# Mega8515_flasher_v2.net
KiCad netlist of a schematic drawn in Altium Designer
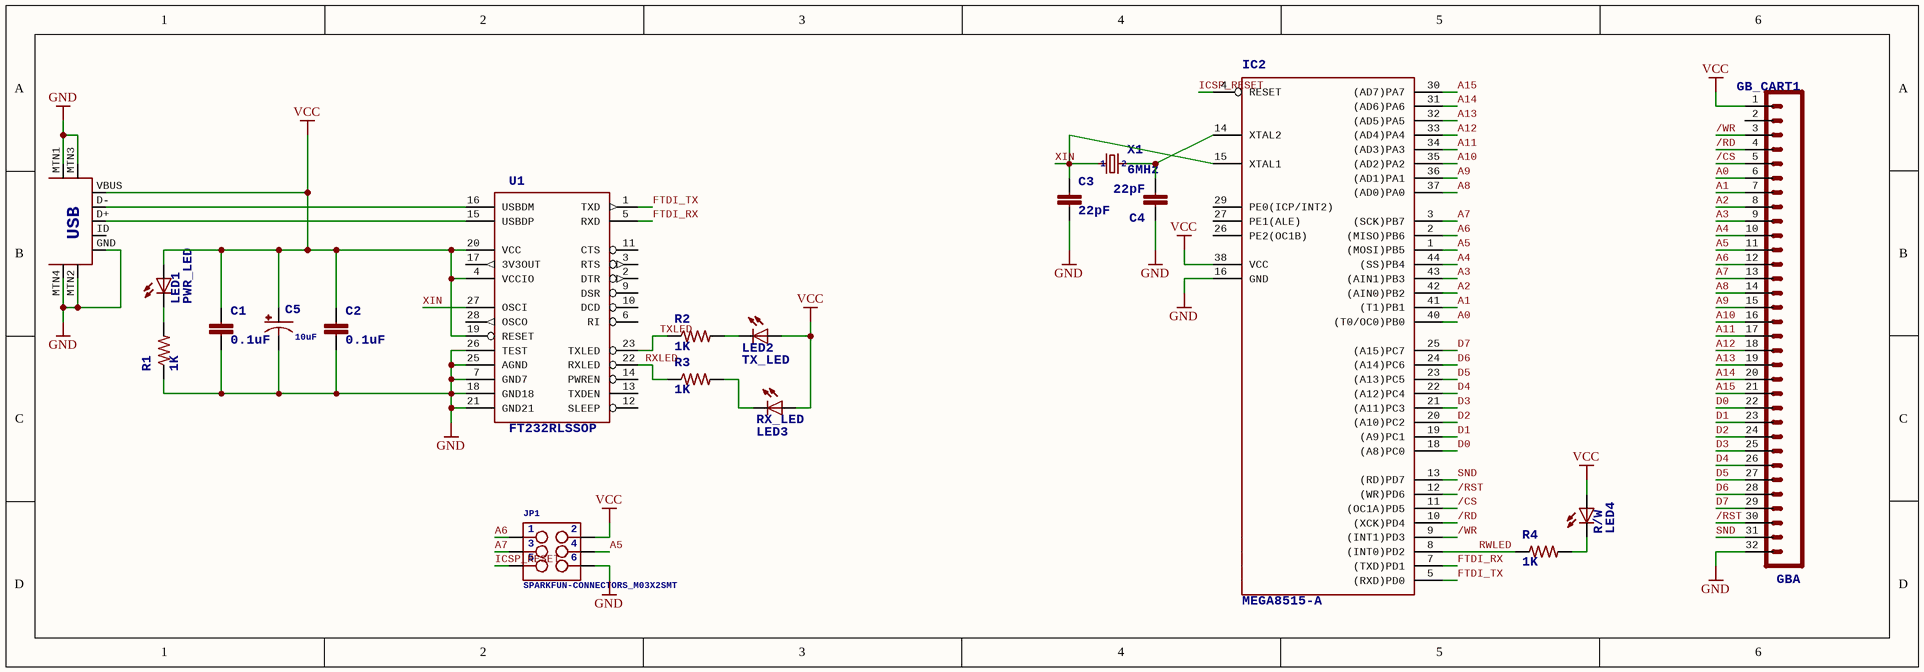
[diagram p0: Mega8515_flasher_v2.SchDoc]

(export (version "E")
  (design (tool "Eeschema 10.0.6"))
  (components
    (comp (ref "C1")
      (value "0.1uF")
      (footprint "0805")
      (description "<b>Capacitor</b>\nStandard 0603 ceramic capacitor, and 0.1\" leaded capacitor.")
      (fields (field (name ">NAME") "C1") (field (name ">VALUE") "0.1uF"))
      (libsource (lib "SparkFun-Capacitors") (part "CAP1206"))
    )
    (comp (ref "C2")
      (value "0.1uF")
      (footprint "0805")
      (description "<b>Capacitor</b>\nStandard 0603 ceramic capacitor, and 0.1\" leaded capacitor.")
      (fields (field (name ">NAME") "C2") (field (name ">VALUE") "0.1uF"))
      (libsource (lib "SparkFun-Capacitors") (part "CAP1206"))
    )
    (comp (ref "C3")
      (value "22pF")
      (footprint "0805")
      (description "<b>Capacitor</b>\nStandard 0603 ceramic capacitor, and 0.1\" leaded capacitor.")
      (fields (field (name ">NAME") "C3") (field (name ">VALUE") "22pF"))
      (libsource (lib "") (part "CAP0805_1"))
    )
    (comp (ref "C4")
      (value "22pF")
      (footprint "0805")
      (description "<b>Capacitor</b>\nStandard 0603 ceramic capacitor, and 0.1\" leaded capacitor.")
      (fields (field (name ">NAME") "C4") (field (name ">VALUE") "22pF"))
      (libsource (lib "SparkFun-Capacitors") (part "CAP0805"))
    )
    (comp (ref "C5")
      (value "10uF")
      (footprint "EIA3216")
      (description "10uF Tantalum SMT<br>\nCAP-00811- 16V 10% (EIA-3216)")
      (fields (field (name ">NAME") "C5"))
      (libsource (lib "SparkFun-Capacitors") (part "10UF-TANT"))
    )
    (comp (ref "GBA")
      (value "GB_CART1")
      (footprint "GB_CART_1")
      (fields (field (name ">VALUE") "GB_CART1") (field (name ">NAME") "GBA"))
      (libsource (lib "alex") (part "GB_CART1"))
    )
    (comp (ref "IC2")
      (value "MEGA8515-A")
      (footprint "TQFP44")
      (fields
        (field (name "MPN") "ATMEGA8515-16AU")
        (field (name ">NAME") "IC2")
        (field (name ">VALUE") "MEGA8515-A")
      )
      (libsource (lib "atmel") (part "MEGA8515-A"))
    )
    (comp (ref "JP1")
      (value "SPARKFUN-CONNECTORS_M03X2SMT")
      (footprint "HDR2X3")
      (fields
        (field (name ">NAME") "JP1")
        (field (name ">VALUE") "SPARKFUN-CONNECTORS_M03X2SMT")
        (field (name "1") "1")
        (field (name "2") "2")
        (field (name "3") "3")
        (field (name "4") "4")
        (field (name "5") "5")
        (field (name "6") "6")
      )
      (libsource (lib "Mega8515_flasher") (part "SPARKFUN-CONNECTORS_M03X2SMT"))
    )
    (comp (ref "LED1")
      (value "PWR_LED")
      (footprint "LED-1206")
      (fields (field (name ">NAME") "LED1") (field (name ">VALUE") "PWR_LED"))
      (libsource (lib "SparkFun-LED") (part "LED1206"))
    )
    (comp (ref "LED2")
      (value "TX_LED")
      (footprint "LED-1206")
      (fields (field (name ">NAME") "LED2") (field (name ">VALUE") "TX_LED"))
      (libsource (lib "SparkFun-LED") (part "LED1206"))
    )
    (comp (ref "R/W")
      (value "LED4")
      (footprint "LED-1206")
      (fields (field (name ">NAME") "R/W") (field (name ">VALUE") "LED4"))
      (libsource (lib "SparkFun-LED") (part "LED1206"))
    )
    (comp (ref "R1")
      (value "1K")
      (footprint "0805")
      (description "<b>Resistor</b>\nBasic schematic elements and footprints for 0603, 1206, and PTH resistors.")
      (fields (field (name ">NAME") "R1") (field (name ">VALUE") "1K"))
      (libsource (lib "SparkFun-Resistors") (part "RESISTOR1206"))
    )
    (comp (ref "R2")
      (value "1K")
      (footprint "0805")
      (description "<b>Resistor</b>\nBasic schematic elements and footprints for 0603, 1206, and PTH resistors.")
      (fields (field (name ">NAME") "R2") (field (name ">VALUE") "1K"))
      (libsource (lib "SparkFun-Resistors") (part "RESISTOR1206"))
    )
    (comp (ref "R3")
      (value "1K")
      (footprint "0805")
      (description "<b>Resistor</b>\nBasic schematic elements and footprints for 0603, 1206, and PTH resistors.")
      (fields (field (name ">NAME") "R3") (field (name ">VALUE") "1K"))
      (libsource (lib "SparkFun-Resistors") (part "RESISTOR1206"))
    )
    (comp (ref "R4")
      (value "1K")
      (footprint "0805")
      (description "<b>Resistor</b>\nBasic schematic elements and footprints for 0603, 1206, and PTH resistors.")
      (fields (field (name ">NAME") "R4") (field (name ">VALUE") "1K"))
      (libsource (lib "SparkFun-Resistors") (part "RESISTOR1206"))
    )
    (comp (ref "RX_LED")
      (value "LED3")
      (footprint "LED-1206")
      (fields (field (name ">NAME") "RX_LED") (field (name ">VALUE") "LED3"))
      (libsource (lib "SparkFun-LED") (part "LED1206"))
    )
    (comp (ref "U1")
      (value "FT232RLSSOP")
      (footprint "SSOP28DB")
      (fields (field (name ">NAME") "U1") (field (name ">VALUE") "FT232RLSSOP"))
      (libsource (lib "SparkFun-DigitalIC") (part "FT232RLSSOP"))
    )
    (comp (ref "USB")
      (value "USB-MINIB-5PIN")
      (footprint "USB-MINIB")
      (fields (field (name "USB") "USB"))
      (libsource (lib "SparkFun-Connectors") (part "USB-MINIB-5PIN"))
    )
    (comp (ref "X1")
      (value "6MHz")
      (footprint "5032")
      (description "Various standard crystals. Proven footprints. Spark Fun Electronics SKU : COM-00534")
      (fields
        (field (name ">NAME") "X1")
        (field (name ">VALUE") "6MHz")
        (field (name "1") "1")
        (field (name "2") "2")
      )
      (libsource (lib "Mega8515_flasher") (part "SPARKFUN-FREQCTRL_CRYSTAL"))
    )
  )
  (nets
    (net (code "1") (name "/A0") (class "Default")
      (node (ref "GBA") (pin "6") (pinfunction "6_6") (pintype "passive"))
      (node (ref "IC2") (pin "40") (pinfunction "(T0/OC0)PB0_40") (pintype "passive"))
    )
    (net (code "2") (name "/A1") (class "Default")
      (node (ref "GBA") (pin "7") (pinfunction "7_7") (pintype "passive"))
      (node (ref "IC2") (pin "41") (pinfunction "(T1)PB1_41") (pintype "passive"))
    )
    (net (code "3") (name "/A2") (class "Default")
      (node (ref "GBA") (pin "8") (pinfunction "8_8") (pintype "passive"))
      (node (ref "IC2") (pin "42") (pinfunction "(AIN0)PB2_42") (pintype "passive"))
    )
    (net (code "4") (name "/A3") (class "Default")
      (node (ref "GBA") (pin "9") (pinfunction "9_9") (pintype "passive"))
      (node (ref "IC2") (pin "43") (pinfunction "(AIN1)PB3_43") (pintype "passive"))
    )
    (net (code "5") (name "/A4") (class "Default")
      (node (ref "GBA") (pin "10") (pinfunction "10_10") (pintype "passive"))
      (node (ref "IC2") (pin "44") (pinfunction "(SS)PB4_44") (pintype "passive"))
    )
    (net (code "6") (name "/A5") (class "Default")
      (node (ref "GBA") (pin "11") (pinfunction "11_11") (pintype "passive"))
      (node (ref "IC2") (pin "1") (pinfunction "(MOSI)PB5_1") (pintype "passive"))
      (node (ref "JP1") (pin "4") (pinfunction "4_4") (pintype "passive"))
    )
    (net (code "7") (name "/A6") (class "Default")
      (node (ref "GBA") (pin "12") (pinfunction "12_12") (pintype "passive"))
      (node (ref "IC2") (pin "2") (pinfunction "(MISO)PB6_2") (pintype "passive"))
      (node (ref "JP1") (pin "1") (pinfunction "1_1") (pintype "passive"))
    )
    (net (code "8") (name "/A7") (class "Default")
      (node (ref "GBA") (pin "13") (pinfunction "13_13") (pintype "passive"))
      (node (ref "IC2") (pin "3") (pinfunction "(SCK)PB7_3") (pintype "passive"))
      (node (ref "JP1") (pin "3") (pinfunction "3_3") (pintype "passive"))
    )
    (net (code "9") (name "/A8") (class "Default")
      (node (ref "GBA") (pin "14") (pinfunction "14_14") (pintype "passive"))
      (node (ref "IC2") (pin "37") (pinfunction "(AD0)PA0_37") (pintype "passive"))
    )
    (net (code "10") (name "/A9") (class "Default")
      (node (ref "GBA") (pin "15") (pinfunction "15_15") (pintype "passive"))
      (node (ref "IC2") (pin "36") (pinfunction "(AD1)PA1_36") (pintype "passive"))
    )
    (net (code "11") (name "/A10") (class "Default")
      (node (ref "GBA") (pin "16") (pinfunction "16_16") (pintype "passive"))
      (node (ref "IC2") (pin "35") (pinfunction "(AD2)PA2_35") (pintype "passive"))
    )
    (net (code "12") (name "/A11") (class "Default")
      (node (ref "GBA") (pin "17") (pinfunction "17_17") (pintype "passive"))
      (node (ref "IC2") (pin "34") (pinfunction "(AD3)PA3_34") (pintype "passive"))
    )
    (net (code "13") (name "/A12") (class "Default")
      (node (ref "GBA") (pin "18") (pinfunction "18_18") (pintype "passive"))
      (node (ref "IC2") (pin "33") (pinfunction "(AD4)PA4_33") (pintype "passive"))
    )
    (net (code "14") (name "/A13") (class "Default")
      (node (ref "GBA") (pin "19") (pinfunction "19_19") (pintype "passive"))
      (node (ref "IC2") (pin "32") (pinfunction "(AD5)PA5_32") (pintype "passive"))
    )
    (net (code "15") (name "/A14") (class "Default")
      (node (ref "GBA") (pin "20") (pinfunction "20_20") (pintype "passive"))
      (node (ref "IC2") (pin "31") (pinfunction "(AD6)PA6_31") (pintype "passive"))
    )
    (net (code "16") (name "/A15") (class "Default")
      (node (ref "GBA") (pin "21") (pinfunction "21_21") (pintype "passive"))
      (node (ref "IC2") (pin "30") (pinfunction "(AD7)PA7_30") (pintype "passive"))
    )
    (net (code "17") (name "/D0") (class "Default")
      (node (ref "GBA") (pin "22") (pinfunction "22_22") (pintype "passive"))
      (node (ref "IC2") (pin "18") (pinfunction "(A8)PC0_18") (pintype "passive"))
    )
    (net (code "18") (name "/D1") (class "Default")
      (node (ref "GBA") (pin "23") (pinfunction "23_23") (pintype "passive"))
      (node (ref "IC2") (pin "19") (pinfunction "(A9)PC1_19") (pintype "passive"))
    )
    (net (code "19") (name "/D2") (class "Default")
      (node (ref "GBA") (pin "24") (pinfunction "24_24") (pintype "passive"))
      (node (ref "IC2") (pin "20") (pinfunction "(A10)PC2_20") (pintype "passive"))
    )
    (net (code "20") (name "/D3") (class "Default")
      (node (ref "GBA") (pin "25") (pinfunction "25_25") (pintype "passive"))
      (node (ref "IC2") (pin "21") (pinfunction "(A11)PC3_21") (pintype "passive"))
    )
    (net (code "21") (name "/D4") (class "Default")
      (node (ref "GBA") (pin "26") (pinfunction "26_26") (pintype "passive"))
      (node (ref "IC2") (pin "22") (pinfunction "(A12)PC4_22") (pintype "passive"))
    )
    (net (code "22") (name "/D5") (class "Default")
      (node (ref "GBA") (pin "27") (pinfunction "27_27") (pintype "passive"))
      (node (ref "IC2") (pin "23") (pinfunction "(A13)PC5_23") (pintype "passive"))
    )
    (net (code "23") (name "/D6") (class "Default")
      (node (ref "GBA") (pin "28") (pinfunction "28_28") (pintype "passive"))
      (node (ref "IC2") (pin "24") (pinfunction "(A14)PC6_24") (pintype "passive"))
    )
    (net (code "24") (name "/D7") (class "Default")
      (node (ref "GBA") (pin "29") (pinfunction "29_29") (pintype "passive"))
      (node (ref "IC2") (pin "25") (pinfunction "(A15)PC7_25") (pintype "passive"))
    )
    (net (code "25") (name "/FTDI_RX") (class "Default")
      (node (ref "IC2") (pin "7") (pinfunction "(TXD)PD1_7") (pintype "passive"))
      (node (ref "U1") (pin "5") (pinfunction "RXD_5") (pintype "passive"))
    )
    (net (code "26") (name "/FTDI_TX") (class "Default")
      (node (ref "IC2") (pin "5") (pinfunction "(RXD)PD0_5") (pintype "passive"))
      (node (ref "U1") (pin "1") (pinfunction "TXD_1") (pintype "output"))
    )
    (net (code "27") (name "/ICSP_RESET") (class "Default")
      (node (ref "IC2") (pin "4") (pinfunction "RESET_4") (pintype "passive"))
      (node (ref "JP1") (pin "5") (pinfunction "5_5") (pintype "passive"))
    )
    (net (code "28") (name "/RWLED") (class "Default")
      (node (ref "IC2") (pin "8") (pinfunction "(INT0)PD2_8") (pintype "passive"))
      (node (ref "R4") (pin "1") (pinfunction "1_1") (pintype "passive"))
    )
    (net (code "29") (name "/RXLED") (class "Default")
      (node (ref "R3") (pin "1") (pinfunction "1_1") (pintype "passive"))
      (node (ref "U1") (pin "22") (pinfunction "RXLED_22") (pintype "passive"))
    )
    (net (code "30") (name "/SND") (class "Default")
      (node (ref "GBA") (pin "31") (pinfunction "31_31") (pintype "passive"))
      (node (ref "IC2") (pin "13") (pinfunction "(RD)PD7_13") (pintype "passive"))
    )
    (net (code "31") (name "/TXLED") (class "Default")
      (node (ref "R2") (pin "1") (pinfunction "1_1") (pintype "passive"))
      (node (ref "U1") (pin "23") (pinfunction "TXLED_23") (pintype "passive"))
    )
    (net (code "32") (name "/XIN") (class "Default")
      (node (ref "C3") (pin "1") (pinfunction "1_1") (pintype "passive"))
      (node (ref "IC2") (pin "15") (pinfunction "XTAL1_15") (pintype "passive"))
      (node (ref "U1") (pin "27") (pinfunction "OSCI_27") (pintype "passive"))
      (node (ref "X1") (pin "1_4") (pinfunction "1_1_4") (pintype "passive"))
    )
    (net (code "33") (name "/{slash}CS") (class "Default")
      (node (ref "GBA") (pin "5") (pinfunction "5_5") (pintype "passive"))
      (node (ref "IC2") (pin "11") (pinfunction "(OC1A)PD5_11") (pintype "passive"))
    )
    (net (code "34") (name "/{slash}RD") (class "Default")
      (node (ref "GBA") (pin "4") (pinfunction "4_4") (pintype "passive"))
      (node (ref "IC2") (pin "10") (pinfunction "(XCK)PD4_10") (pintype "passive"))
    )
    (net (code "35") (name "/{slash}RST") (class "Default")
      (node (ref "GBA") (pin "30") (pinfunction "30_30") (pintype "passive"))
      (node (ref "IC2") (pin "12") (pinfunction "(WR)PD6_12") (pintype "passive"))
    )
    (net (code "36") (name "/{slash}WR") (class "Default")
      (node (ref "GBA") (pin "3") (pinfunction "3_3") (pintype "passive"))
      (node (ref "IC2") (pin "9") (pinfunction "(INT1)PD3_9") (pintype "passive"))
    )
    (net (code "37") (name "GND") (class "Default")
      (node (ref "C1") (pin "2") (pinfunction "2_2") (pintype "passive"))
      (node (ref "C2") (pin "2") (pinfunction "2_2") (pintype "passive"))
      (node (ref "C3") (pin "2") (pinfunction "2_2") (pintype "passive"))
      (node (ref "C4") (pin "1") (pinfunction "1_1") (pintype "passive"))
      (node (ref "C5") (pin "C") (pinfunction "-_C") (pintype "passive"))
      (node (ref "GBA") (pin "32") (pinfunction "32_32") (pintype "passive"))
      (node (ref "IC2") (pin "16") (pinfunction "GND_16") (pintype "power_in"))
      (node (ref "JP1") (pin "6") (pinfunction "6_6") (pintype "passive"))
      (node (ref "R1") (pin "1") (pinfunction "1_1") (pintype "passive"))
      (node (ref "U1") (pin "18") (pinfunction "GND18_18") (pintype "power_in"))
      (node (ref "U1") (pin "21") (pinfunction "GND21_21") (pintype "power_in"))
      (node (ref "U1") (pin "25") (pinfunction "AGND_25") (pintype "power_in"))
      (node (ref "U1") (pin "26") (pinfunction "TEST_26") (pintype "passive"))
      (node (ref "U1") (pin "7") (pinfunction "GND7_7") (pintype "power_in"))
      (node (ref "USB") (pin "GND") (pinfunction "GND_GND") (pintype "passive"))
      (node (ref "USB") (pin "MTN1") (pinfunction "MTN2_MTN1") (pintype "passive"))
      (node (ref "USB") (pin "MTN2") (pinfunction "MTN3_MTN2") (pintype "passive"))
      (node (ref "USB") (pin "MTN3") (pinfunction "MTN1_MTN3") (pintype "passive"))
      (node (ref "USB") (pin "MTN4") (pinfunction "MTN4_MTN4") (pintype "passive"))
    )
    (net (code "38") (name "Net-(IC2-XTAL2)") (class "Default")
      (node (ref "C4") (pin "2") (pinfunction "2_2") (pintype "passive"))
      (node (ref "IC2") (pin "14") (pinfunction "XTAL2_14") (pintype "passive"))
      (node (ref "X1") (pin "2_3") (pinfunction "2_2_3") (pintype "passive"))
    )
    (net (code "39") (name "Net-(LED1-PadC)") (class "Default")
      (node (ref "LED1") (pin "C") (pinfunction "C_C") (pintype "passive"))
      (node (ref "R1") (pin "2") (pinfunction "2_2") (pintype "passive"))
    )
    (net (code "40") (name "Net-(LED2-PadC)") (class "Default")
      (node (ref "LED2") (pin "C") (pinfunction "C_C") (pintype "passive"))
      (node (ref "R2") (pin "2") (pinfunction "2_2") (pintype "passive"))
    )
    (net (code "41") (name "Net-(R/W-PadC)") (class "Default")
      (node (ref "R/W") (pin "C") (pinfunction "C_C") (pintype "passive"))
      (node (ref "R4") (pin "2") (pinfunction "2_2") (pintype "passive"))
    )
    (net (code "42") (name "Net-(R3-Pad2)") (class "Default")
      (node (ref "R3") (pin "2") (pinfunction "2_2") (pintype "passive"))
      (node (ref "RX_LED") (pin "C") (pinfunction "C_C") (pintype "passive"))
    )
    (net (code "43") (name "Net-(U1-USBDM)") (class "Default")
      (node (ref "U1") (pin "16") (pinfunction "USBDM_16") (pintype "passive"))
      (node (ref "USB") (pin "D-") (pinfunction "D-_D-") (pintype "passive"))
    )
    (net (code "44") (name "Net-(U1-USBDP)") (class "Default")
      (node (ref "U1") (pin "15") (pinfunction "USBDP_15") (pintype "passive"))
      (node (ref "USB") (pin "D+") (pinfunction "D+_D+") (pintype "passive"))
    )
    (net (code "45") (name "VCC") (class "Default")
      (node (ref "C1") (pin "1") (pinfunction "1_1") (pintype "passive"))
      (node (ref "C2") (pin "1") (pinfunction "1_1") (pintype "passive"))
      (node (ref "C5") (pin "A") (pinfunction "+_A") (pintype "passive"))
      (node (ref "GBA") (pin "1") (pinfunction "1_1") (pintype "passive"))
      (node (ref "IC2") (pin "38") (pinfunction "VCC_38") (pintype "power_in"))
      (node (ref "JP1") (pin "2") (pinfunction "2_2") (pintype "passive"))
      (node (ref "LED1") (pin "A") (pinfunction "A_A") (pintype "passive"))
      (node (ref "LED2") (pin "A") (pinfunction "A_A") (pintype "passive"))
      (node (ref "R/W") (pin "A") (pinfunction "A_A") (pintype "passive"))
      (node (ref "RX_LED") (pin "A") (pinfunction "A_A") (pintype "passive"))
      (node (ref "U1") (pin "19") (pinfunction "RESET_19") (pintype "passive"))
      (node (ref "U1") (pin "20") (pinfunction "VCC_20") (pintype "power_in"))
      (node (ref "U1") (pin "4") (pinfunction "VCCIO_4") (pintype "power_in"))
      (node (ref "USB") (pin "VBUS") (pinfunction "VBUS_VBUS") (pintype "passive"))
    )
    (net (code "46") (name "unconnected-(GBA-Pad2)") (class "Default")
      (node (ref "GBA") (pin "2") (pinfunction "2_2") (pintype "passive"))
    )
    (net (code "47") (name "unconnected-(IC2-NC1-Pad6)") (class "Default")
      (node (ref "IC2") (pin "6") (pinfunction "NC1_6") (pintype "passive"))
    )
    (net (code "48") (name "unconnected-(IC2-NC2-Pad17)") (class "Default")
      (node (ref "IC2") (pin "17") (pinfunction "NC2_17") (pintype "passive"))
    )
    (net (code "49") (name "unconnected-(IC2-NC3-Pad28)") (class "Default")
      (node (ref "IC2") (pin "28") (pinfunction "NC3_28") (pintype "passive"))
    )
    (net (code "50") (name "unconnected-(IC2-NC4-Pad39)") (class "Default")
      (node (ref "IC2") (pin "39") (pinfunction "NC4_39") (pintype "passive"))
    )
    (net (code "51") (name "unconnected-(IC2-PE0(ICP{slash}INT2)-Pad29)") (class "Default")
      (node (ref "IC2") (pin "29") (pinfunction "PE0(ICP/INT2)_29") (pintype "passive"))
    )
    (net (code "52") (name "unconnected-(IC2-PE1(ALE)-Pad27)") (class "Default")
      (node (ref "IC2") (pin "27") (pinfunction "PE1(ALE)_27") (pintype "passive"))
    )
    (net (code "53") (name "unconnected-(IC2-PE2(OC1B)-Pad26)") (class "Default")
      (node (ref "IC2") (pin "26") (pinfunction "PE2(OC1B)_26") (pintype "passive"))
    )
    (net (code "54") (name "unconnected-(U1-3V3OUT-Pad17)") (class "Default")
      (node (ref "U1") (pin "17") (pinfunction "3V3OUT_17") (pintype "output"))
    )
    (net (code "55") (name "unconnected-(U1-CTS-Pad11)") (class "Default")
      (node (ref "U1") (pin "11") (pinfunction "CTS_11") (pintype "passive"))
    )
    (net (code "56") (name "unconnected-(U1-DCD-Pad10)") (class "Default")
      (node (ref "U1") (pin "10") (pinfunction "DCD_10") (pintype "passive"))
    )
    (net (code "57") (name "unconnected-(U1-DSR-Pad9)") (class "Default")
      (node (ref "U1") (pin "9") (pinfunction "DSR_9") (pintype "passive"))
    )
    (net (code "58") (name "unconnected-(U1-DTR-Pad2)") (class "Default")
      (node (ref "U1") (pin "2") (pinfunction "DTR_2") (pintype "output"))
    )
    (net (code "59") (name "unconnected-(U1-OSCO-Pad28)") (class "Default")
      (node (ref "U1") (pin "28") (pinfunction "OSCO_28") (pintype "output"))
    )
    (net (code "60") (name "unconnected-(U1-PWREN-Pad14)") (class "Default")
      (node (ref "U1") (pin "14") (pinfunction "PWREN_14") (pintype "passive"))
    )
    (net (code "61") (name "unconnected-(U1-RI-Pad6)") (class "Default")
      (node (ref "U1") (pin "6") (pinfunction "RI_6") (pintype "passive"))
    )
    (net (code "62") (name "unconnected-(U1-RTS-Pad3)") (class "Default")
      (node (ref "U1") (pin "3") (pinfunction "RTS_3") (pintype "output"))
    )
    (net (code "63") (name "unconnected-(U1-SLEEP-Pad12)") (class "Default")
      (node (ref "U1") (pin "12") (pinfunction "SLEEP_12") (pintype "passive"))
    )
    (net (code "64") (name "unconnected-(U1-TXDEN-Pad13)") (class "Default")
      (node (ref "U1") (pin "13") (pinfunction "TXDEN_13") (pintype "passive"))
    )
    (net (code "65") (name "unconnected-(USB-PadID)") (class "Default")
      (node (ref "USB") (pin "ID") (pinfunction "ID_ID") (pintype "passive"))
    )
  )
)
